# FRONT_PL_v1.net
KiCad netlist of a schematic drawn in Altium Designer
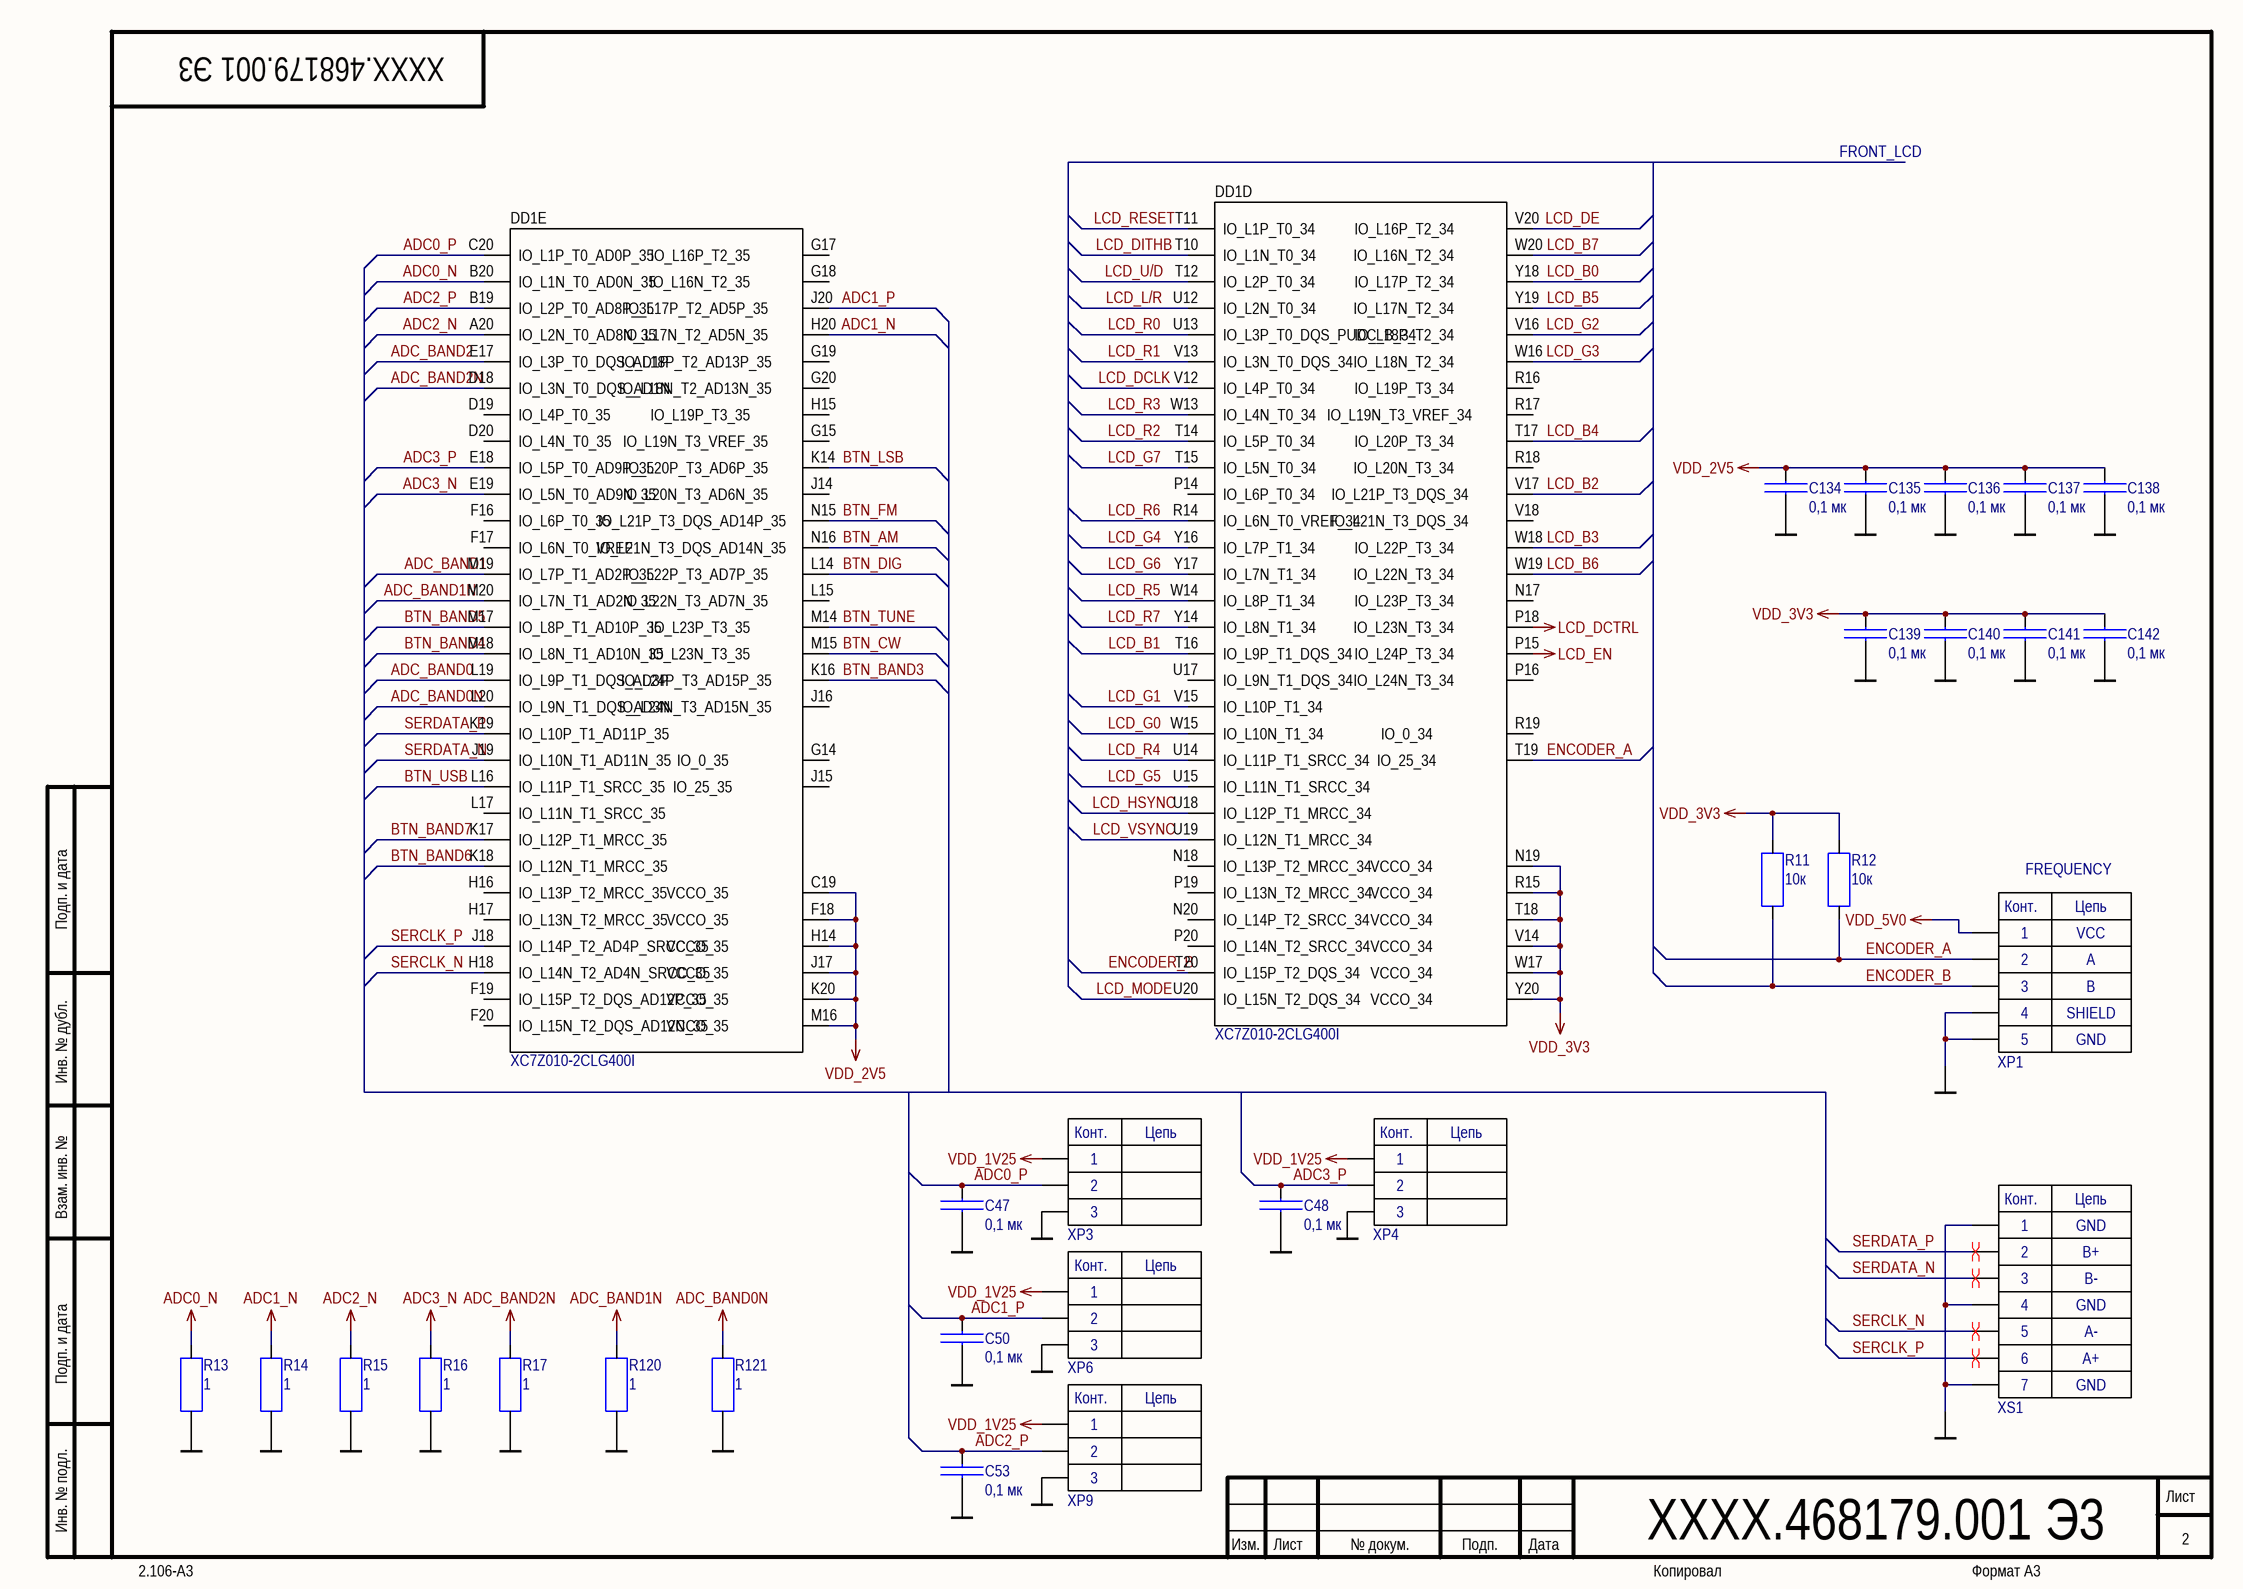
[diagram p0: FRONT_PL_v1.SchDoc]

(export (version "E")
  (design (tool "Eeschema 10.0.6"))
  (components
    (comp (ref "C47")
      (value "CC0402KRX5R6BB104")
      (footprint "CAPC1005X05L")
      (description "ЧИП конденсатор")
      (fields
        (field (name "NOMINAL") "0,1 мк")
        (field (name "MANUFACTURER") "Yageo")
        (field (name "TOLERANCE") "10%")
      )
      (libsource (lib "Database_Gost") (part "Capacitor const"))
    )
    (comp (ref "C48")
      (value "CC0402KRX5R6BB104")
      (footprint "CAPC1005X05L")
      (description "ЧИП конденсатор")
      (fields
        (field (name "NOMINAL") "0,1 мк")
        (field (name "MANUFACTURER") "Yageo")
        (field (name "TOLERANCE") "10%")
      )
      (libsource (lib "Database_Gost") (part "Capacitor const"))
    )
    (comp (ref "C50")
      (value "CC0402KRX5R6BB104")
      (footprint "CAPC1005X05L")
      (description "ЧИП конденсатор")
      (fields
        (field (name "NOMINAL") "0,1 мк")
        (field (name "MANUFACTURER") "Yageo")
        (field (name "TOLERANCE") "10%")
      )
      (libsource (lib "Database_Gost") (part "Capacitor const"))
    )
    (comp (ref "C53")
      (value "CC0402KRX5R6BB104")
      (footprint "CAPC1005X05L")
      (description "ЧИП конденсатор")
      (fields
        (field (name "NOMINAL") "0,1 мк")
        (field (name "MANUFACTURER") "Yageo")
        (field (name "TOLERANCE") "10%")
      )
      (libsource (lib "Database_Gost") (part "Capacitor const"))
    )
    (comp (ref "C134")
      (value "CC0402KRX5R6BB104")
      (footprint "CAPC1005X05L")
      (description "ЧИП конденсатор")
      (fields
        (field (name "NOMINAL") "0,1 мк")
        (field (name "MANUFACTURER") "Yageo")
        (field (name "TOLERANCE") "10%")
      )
      (libsource (lib "Database_Gost") (part "Capacitor const"))
    )
    (comp (ref "C135")
      (value "CC0402KRX5R6BB104")
      (footprint "CAPC1005X05L")
      (description "ЧИП конденсатор")
      (fields
        (field (name "NOMINAL") "0,1 мк")
        (field (name "MANUFACTURER") "Yageo")
        (field (name "TOLERANCE") "10%")
      )
      (libsource (lib "Database_Gost") (part "Capacitor const"))
    )
    (comp (ref "C136")
      (value "CC0402KRX5R6BB104")
      (footprint "CAPC1005X05L")
      (description "ЧИП конденсатор")
      (fields
        (field (name "NOMINAL") "0,1 мк")
        (field (name "MANUFACTURER") "Yageo")
        (field (name "TOLERANCE") "10%")
      )
      (libsource (lib "Database_Gost") (part "Capacitor const"))
    )
    (comp (ref "C137")
      (value "CC0402KRX5R6BB104")
      (footprint "CAPC1005X05L")
      (description "ЧИП конденсатор")
      (fields
        (field (name "NOMINAL") "0,1 мк")
        (field (name "MANUFACTURER") "Yageo")
        (field (name "TOLERANCE") "10%")
      )
      (libsource (lib "Database_Gost") (part "Capacitor const"))
    )
    (comp (ref "C138")
      (value "CC0402KRX5R6BB104")
      (footprint "CAPC1005X05L")
      (description "ЧИП конденсатор")
      (fields
        (field (name "NOMINAL") "0,1 мк")
        (field (name "MANUFACTURER") "Yageo")
        (field (name "TOLERANCE") "10%")
      )
      (libsource (lib "Database_Gost") (part "Capacitor const"))
    )
    (comp (ref "C139")
      (value "CC0402KRX5R6BB104")
      (footprint "CAPC1005X05L")
      (description "ЧИП конденсатор")
      (fields
        (field (name "NOMINAL") "0,1 мк")
        (field (name "MANUFACTURER") "Yageo")
        (field (name "TOLERANCE") "10%")
      )
      (libsource (lib "Database_Gost") (part "Capacitor const"))
    )
    (comp (ref "C140")
      (value "CC0402KRX5R6BB104")
      (footprint "CAPC1005X05L")
      (description "ЧИП конденсатор")
      (fields
        (field (name "NOMINAL") "0,1 мк")
        (field (name "MANUFACTURER") "Yageo")
        (field (name "TOLERANCE") "10%")
      )
      (libsource (lib "Database_Gost") (part "Capacitor const"))
    )
    (comp (ref "C141")
      (value "CC0402KRX5R6BB104")
      (footprint "CAPC1005X05L")
      (description "ЧИП конденсатор")
      (fields
        (field (name "NOMINAL") "0,1 мк")
        (field (name "MANUFACTURER") "Yageo")
        (field (name "TOLERANCE") "10%")
      )
      (libsource (lib "Database_Gost") (part "Capacitor const"))
    )
    (comp (ref "C142")
      (value "CC0402KRX5R6BB104")
      (footprint "CAPC1005X05L")
      (description "ЧИП конденсатор")
      (fields
        (field (name "NOMINAL") "0,1 мк")
        (field (name "MANUFACTURER") "Yageo")
        (field (name "TOLERANCE") "10%")
      )
      (libsource (lib "Database_Gost") (part "Capacitor const"))
    )
    (comp (ref "DD1")
      (value "XC7Z010-2CLG400I")
      (footprint "BGA400C80P20X20_1700X1700X147")
      (description "Zynq®-7000 SoC Family")
      (fields (field (name "MANUFACTURER") "Xilinx"))
      (libsource (lib "Chips_single") (part "XC7Z010-2CLG400I"))
    )
    (comp (ref "R11")
      (value "RC0402JR-0710KL")
      (footprint "RESC1005X04L")
      (description "ЧИП резистор")
      (fields
        (field (name "NOMINAL") "10к")
        (field (name "MANUFACTURER") "Yageo")
        (field (name "TOLERANCE") "5%")
      )
      (libsource (lib "Database_Gost") (part "Resistor const"))
    )
    (comp (ref "R12")
      (value "RC0402JR-0710KL")
      (footprint "RESC1005X04L")
      (description "ЧИП резистор")
      (fields
        (field (name "NOMINAL") "10к")
        (field (name "MANUFACTURER") "Yageo")
        (field (name "TOLERANCE") "5%")
      )
      (libsource (lib "Database_Gost") (part "Resistor const"))
    )
    (comp (ref "R13")
      (value "RC0402JR-071RL")
      (footprint "RESC1005X04L")
      (description "ЧИП резистор")
      (fields
        (field (name "NOMINAL") "1")
        (field (name "MANUFACTURER") "Yageo")
        (field (name "TOLERANCE") "5%")
      )
      (libsource (lib "Database_Gost") (part "Resistor const"))
    )
    (comp (ref "R14")
      (value "RC0402JR-071RL")
      (footprint "RESC1005X04L")
      (description "ЧИП резистор")
      (fields
        (field (name "NOMINAL") "1")
        (field (name "MANUFACTURER") "Yageo")
        (field (name "TOLERANCE") "5%")
      )
      (libsource (lib "Database_Gost") (part "Resistor const"))
    )
    (comp (ref "R15")
      (value "RC0402JR-071RL")
      (footprint "RESC1005X04L")
      (description "ЧИП резистор")
      (fields
        (field (name "NOMINAL") "1")
        (field (name "MANUFACTURER") "Yageo")
        (field (name "TOLERANCE") "5%")
      )
      (libsource (lib "Database_Gost") (part "Resistor const"))
    )
    (comp (ref "R16")
      (value "RC0402JR-071RL")
      (footprint "RESC1005X04L")
      (description "ЧИП резистор")
      (fields
        (field (name "NOMINAL") "1")
        (field (name "MANUFACTURER") "Yageo")
        (field (name "TOLERANCE") "5%")
      )
      (libsource (lib "Database_Gost") (part "Resistor const"))
    )
    (comp (ref "R17")
      (value "RC0402JR-071RL")
      (footprint "RESC1005X04L")
      (description "ЧИП резистор")
      (fields
        (field (name "NOMINAL") "1")
        (field (name "MANUFACTURER") "Yageo")
        (field (name "TOLERANCE") "5%")
      )
      (libsource (lib "Database_Gost") (part "Resistor const"))
    )
    (comp (ref "R120")
      (value "RC0402JR-071RL")
      (footprint "RESC1005X04L")
      (description "ЧИП резистор")
      (fields
        (field (name "NOMINAL") "1")
        (field (name "MANUFACTURER") "Yageo")
        (field (name "TOLERANCE") "5%")
      )
      (libsource (lib "Database_Gost") (part "Resistor const"))
    )
    (comp (ref "R121")
      (value "RC0402JR-071RL")
      (footprint "RESC1005X04L")
      (description "ЧИП резистор")
      (fields
        (field (name "NOMINAL") "1")
        (field (name "MANUFACTURER") "Yageo")
        (field (name "TOLERANCE") "5%")
      )
      (libsource (lib "Database_Gost") (part "Resistor const"))
    )
    (comp (ref "XP1")
      (value "WB-05")
      (footprint "WB-05 (MW-5M) pitch 2.00mm")
      (description "WB-05 (MW-5M) pitch 2.00mm\r\nDS1066-05M")
      (libsource (lib "Connectors") (part "WB-05"))
    )
    (comp (ref "XP3")
      (value "WB-03")
      (footprint "WB-03 (MW-3M) PITCH 2.00MM")
      (description "WB-03(MW-3M) pitch 2.00mm\r\nDS1066-03M")
      (libsource (lib "Connectors") (part "WB-03"))
    )
    (comp (ref "XP4")
      (value "WB-03")
      (footprint "WB-03 (MW-3M) PITCH 2.00MM")
      (description "WB-03(MW-3M) pitch 2.00mm\r\nDS1066-03M")
      (libsource (lib "Connectors") (part "WB-03"))
    )
    (comp (ref "XP6")
      (value "WB-03")
      (footprint "WB-03 (MW-3M) PITCH 2.00MM")
      (description "WB-03(MW-3M) pitch 2.00mm\r\nDS1066-03M")
      (libsource (lib "Connectors") (part "WB-03"))
    )
    (comp (ref "XP9")
      (value "WB-03")
      (footprint "WB-03 (MW-3M) PITCH 2.00MM")
      (description "WB-03(MW-3M) pitch 2.00mm\r\nDS1066-03M")
      (libsource (lib "Connectors") (part "WB-03"))
    )
    (comp (ref "XS1")
      (value "KLS1-SATA001")
      (footprint "KLS1-SATA001")
      (description "SATA Type A 7P Male Connector,SMD")
      (libsource (lib "Connectors") (part "SATA KLS1-SATA001"))
    )
  )
  (nets
    (net (code "1") (name "/ADC0_P") (class "Default")
      (node (ref "C47") (pin "2") (pinfunction "2_2") (pintype "passive"))
      (node (ref "DD1") (pin "C20") (pinfunction "IO_L1P_T0_AD0P_35_C20") (pintype "passive"))
      (node (ref "XP3") (pin "2") (pinfunction "2_2") (pintype "passive"))
    )
    (net (code "2") (name "/ADC1_P") (class "Default")
      (node (ref "C50") (pin "2") (pinfunction "2_2") (pintype "passive"))
      (node (ref "DD1") (pin "J20") (pinfunction "IO_L17P_T2_AD5P_35_J20") (pintype "passive"))
      (node (ref "XP6") (pin "2") (pinfunction "2_2") (pintype "passive"))
    )
    (net (code "3") (name "/ADC2_P") (class "Default")
      (node (ref "C53") (pin "2") (pinfunction "2_2") (pintype "passive"))
      (node (ref "DD1") (pin "B19") (pinfunction "IO_L2P_T0_AD8P_35_B19") (pintype "passive"))
      (node (ref "XP9") (pin "2") (pinfunction "2_2") (pintype "passive"))
    )
    (net (code "4") (name "/ADC3_P") (class "Default")
      (node (ref "C48") (pin "2") (pinfunction "2_2") (pintype "passive"))
      (node (ref "DD1") (pin "E18") (pinfunction "IO_L5P_T0_AD9P_35_E18") (pintype "passive"))
      (node (ref "XP4") (pin "2") (pinfunction "2_2") (pintype "passive"))
    )
    (net (code "5") (name "/ADC_BAND0") (class "Default")
      (node (ref "DD1") (pin "L19") (pinfunction "IO_L9P_T1_DQS_AD3P_L19") (pintype "passive"))
    )
    (net (code "6") (name "/ADC_BAND1") (class "Default")
      (node (ref "DD1") (pin "M19") (pinfunction "IO_L7P_T1_AD2P_35_M19") (pintype "passive"))
    )
    (net (code "7") (name "/ADC_BAND2") (class "Default")
      (node (ref "DD1") (pin "E17") (pinfunction "IO_L3P_T0_DQS_AD1P_E17") (pintype "passive"))
    )
    (net (code "8") (name "/BTN_AM") (class "Default")
      (node (ref "DD1") (pin "N16") (pinfunction "IO_L21N_T3_DQS_AD14N_35_N16") (pintype "passive"))
    )
    (net (code "9") (name "/BTN_BAND3") (class "Default")
      (node (ref "DD1") (pin "K16") (pinfunction "IO_L24P_T3_AD15P_35_K16") (pintype "passive"))
    )
    (net (code "10") (name "/BTN_BAND4") (class "Default")
      (node (ref "DD1") (pin "M18") (pinfunction "IO_L8N_T1_AD10N_35_M18") (pintype "passive"))
    )
    (net (code "11") (name "/BTN_BAND5") (class "Default")
      (node (ref "DD1") (pin "M17") (pinfunction "IO_L8P_T1_AD10P_35_M17") (pintype "passive"))
    )
    (net (code "12") (name "/BTN_BAND6") (class "Default")
      (node (ref "DD1") (pin "K18") (pinfunction "IO_L12N_T1_MRCC_35_K18") (pintype "passive"))
    )
    (net (code "13") (name "/BTN_BAND7") (class "Default")
      (node (ref "DD1") (pin "K17") (pinfunction "IO_L12P_T1_MRCC_35_K17") (pintype "passive"))
    )
    (net (code "14") (name "/BTN_CW") (class "Default")
      (node (ref "DD1") (pin "M15") (pinfunction "IO_L23N_T3_35_M15") (pintype "passive"))
    )
    (net (code "15") (name "/BTN_DIG") (class "Default")
      (node (ref "DD1") (pin "L14") (pinfunction "IO_L22P_T3_AD7P_35_L14") (pintype "passive"))
    )
    (net (code "16") (name "/BTN_FM") (class "Default")
      (node (ref "DD1") (pin "N15") (pinfunction "IO_L21P_T3_DQS_AD14P_35_N15") (pintype "passive"))
    )
    (net (code "17") (name "/BTN_LSB") (class "Default")
      (node (ref "DD1") (pin "K14") (pinfunction "IO_L20P_T3_AD6P_35_K14") (pintype "passive"))
    )
    (net (code "18") (name "/BTN_TUNE") (class "Default")
      (node (ref "DD1") (pin "M14") (pinfunction "IO_L23P_T3_35_M14") (pintype "passive"))
    )
    (net (code "19") (name "/BTN_USB") (class "Default")
      (node (ref "DD1") (pin "L16") (pinfunction "IO_L11P_T1_SRCC_35_L16") (pintype "passive"))
    )
    (net (code "20") (name "/ENCODER_A") (class "Default")
      (node (ref "DD1") (pin "T19") (pinfunction "IO_25_34_T19") (pintype "open_collector"))
      (node (ref "R12") (pin "2") (pinfunction "2_2") (pintype "passive"))
      (node (ref "XP1") (pin "2") (pinfunction "2_2") (pintype "passive"))
    )
    (net (code "21") (name "/ENCODER_B") (class "Default")
      (node (ref "DD1") (pin "T20") (pinfunction "IO_L15P_T2_DQS_34_T20") (pintype "open_collector"))
      (node (ref "R11") (pin "2") (pinfunction "2_2") (pintype "passive"))
      (node (ref "XP1") (pin "3") (pinfunction "3_3") (pintype "passive"))
    )
    (net (code "22") (name "/LCD_B0") (class "Default")
      (node (ref "DD1") (pin "Y18") (pinfunction "IO_L17P_T2_34_Y18") (pintype "open_collector"))
    )
    (net (code "23") (name "/LCD_B1") (class "Default")
      (node (ref "DD1") (pin "T16") (pinfunction "IO_L9P_T1_DQS_34_T16") (pintype "open_collector"))
    )
    (net (code "24") (name "/LCD_B2") (class "Default")
      (node (ref "DD1") (pin "V17") (pinfunction "IO_L21P_T3_DQS_34_V17") (pintype "open_collector"))
    )
    (net (code "25") (name "/LCD_B3") (class "Default")
      (node (ref "DD1") (pin "W18") (pinfunction "IO_L22P_T3_34_W18") (pintype "open_collector"))
    )
    (net (code "26") (name "/LCD_B4") (class "Default")
      (node (ref "DD1") (pin "T17") (pinfunction "IO_L20P_T3_34_T17") (pintype "open_collector"))
    )
    (net (code "27") (name "/LCD_B5") (class "Default")
      (node (ref "DD1") (pin "Y19") (pinfunction "IO_L17N_T2_34_Y19") (pintype "open_collector"))
    )
    (net (code "28") (name "/LCD_B6") (class "Default")
      (node (ref "DD1") (pin "W19") (pinfunction "IO_L22N_T3_34_W19") (pintype "open_collector"))
    )
    (net (code "29") (name "/LCD_B7") (class "Default")
      (node (ref "DD1") (pin "W20") (pinfunction "IO_L16N_T2_34_W20") (pintype "open_collector"))
    )
    (net (code "30") (name "/LCD_DCLK") (class "Default")
      (node (ref "DD1") (pin "V12") (pinfunction "IO_L4P_T0_34_V12") (pintype "open_collector"))
    )
    (net (code "31") (name "/LCD_DE") (class "Default")
      (node (ref "DD1") (pin "V20") (pinfunction "IO_L16P_T2_34_V20") (pintype "open_collector"))
    )
    (net (code "32") (name "/LCD_DITHB") (class "Default")
      (node (ref "DD1") (pin "T10") (pinfunction "IO_L1N_T0_34_T10") (pintype "open_collector"))
    )
    (net (code "33") (name "/LCD_G0") (class "Default")
      (node (ref "DD1") (pin "W15") (pinfunction "IO_L10N_T1_34_W15") (pintype "open_collector"))
    )
    (net (code "34") (name "/LCD_G1") (class "Default")
      (node (ref "DD1") (pin "V15") (pinfunction "IO_L10P_T1_34_V15") (pintype "open_collector"))
    )
    (net (code "35") (name "/LCD_G2") (class "Default")
      (node (ref "DD1") (pin "V16") (pinfunction "IO_L18P_T2_34_V16") (pintype "open_collector"))
    )
    (net (code "36") (name "/LCD_G3") (class "Default")
      (node (ref "DD1") (pin "W16") (pinfunction "IO_L18N_T2_34_W16") (pintype "open_collector"))
    )
    (net (code "37") (name "/LCD_G4") (class "Default")
      (node (ref "DD1") (pin "Y16") (pinfunction "IO_L7P_T1_34_Y16") (pintype "open_collector"))
    )
    (net (code "38") (name "/LCD_G5") (class "Default")
      (node (ref "DD1") (pin "U15") (pinfunction "IO_L11N_T1_SRCC_34_U15") (pintype "open_collector"))
    )
    (net (code "39") (name "/LCD_G6") (class "Default")
      (node (ref "DD1") (pin "Y17") (pinfunction "IO_L7N_T1_34_Y17") (pintype "open_collector"))
    )
    (net (code "40") (name "/LCD_G7") (class "Default")
      (node (ref "DD1") (pin "T15") (pinfunction "IO_L5N_T0_34_T15") (pintype "open_collector"))
    )
    (net (code "41") (name "/LCD_HSYNC") (class "Default")
      (node (ref "DD1") (pin "U18") (pinfunction "IO_L12P_T1_MRCC_34_U18") (pintype "open_collector"))
    )
    (net (code "42") (name "/LCD_L{slash}R") (class "Default")
      (node (ref "DD1") (pin "U12") (pinfunction "IO_L2N_T0_34_U12") (pintype "open_collector"))
    )
    (net (code "43") (name "/LCD_MODE") (class "Default")
      (node (ref "DD1") (pin "U20") (pinfunction "IO_L15N_T2_DQS_34_U20") (pintype "open_collector"))
    )
    (net (code "44") (name "/LCD_R0") (class "Default")
      (node (ref "DD1") (pin "U13") (pinfunction "IO_L3P_T0_DQS_PUDC_B_34_U13") (pintype "open_collector"))
    )
    (net (code "45") (name "/LCD_R1") (class "Default")
      (node (ref "DD1") (pin "V13") (pinfunction "IO_L3N_T0_DQS_34_V13") (pintype "open_collector"))
    )
    (net (code "46") (name "/LCD_R2") (class "Default")
      (node (ref "DD1") (pin "T14") (pinfunction "IO_L5P_T0_34_T14") (pintype "open_collector"))
    )
    (net (code "47") (name "/LCD_R3") (class "Default")
      (node (ref "DD1") (pin "W13") (pinfunction "IO_L4N_T0_34_W13") (pintype "open_collector"))
    )
    (net (code "48") (name "/LCD_R4") (class "Default")
      (node (ref "DD1") (pin "U14") (pinfunction "IO_L11P_T1_SRCC_34_U14") (pintype "open_collector"))
    )
    (net (code "49") (name "/LCD_R5") (class "Default")
      (node (ref "DD1") (pin "W14") (pinfunction "IO_L8P_T1_34_W14") (pintype "open_collector"))
    )
    (net (code "50") (name "/LCD_R6") (class "Default")
      (node (ref "DD1") (pin "R14") (pinfunction "IO_L6N_T0_VREF_34_R14") (pintype "open_collector"))
    )
    (net (code "51") (name "/LCD_R7") (class "Default")
      (node (ref "DD1") (pin "Y14") (pinfunction "IO_L8N_T1_34_Y14") (pintype "open_collector"))
    )
    (net (code "52") (name "/LCD_RESET") (class "Default")
      (node (ref "DD1") (pin "T11") (pinfunction "IO_L1P_T0_34_T11") (pintype "open_collector"))
    )
    (net (code "53") (name "/LCD_U{slash}D") (class "Default")
      (node (ref "DD1") (pin "T12") (pinfunction "IO_L2P_T0_34_T12") (pintype "open_collector"))
    )
    (net (code "54") (name "/LCD_VSYNC") (class "Default")
      (node (ref "DD1") (pin "U19") (pinfunction "IO_L12N_T1_MRCC_34_U19") (pintype "open_collector"))
    )
    (net (code "55") (name "/SERCLK_N") (class "Default")
      (node (ref "DD1") (pin "H18") (pinfunction "IO_L14N_T2_AD4N_SRCC_35_H18") (pintype "passive"))
      (node (ref "XS1") (pin "5") (pinfunction "5_5") (pintype "passive"))
    )
    (net (code "56") (name "/SERCLK_P") (class "Default")
      (node (ref "DD1") (pin "J18") (pinfunction "IO_L14P_T2_AD4P_SRCC_35_J18") (pintype "passive"))
      (node (ref "XS1") (pin "6") (pinfunction "6_6") (pintype "passive"))
    )
    (net (code "57") (name "/SERDATA_N") (class "Default")
      (node (ref "DD1") (pin "J19") (pinfunction "IO_L10N_T1_AD11N_35_J19") (pintype "passive"))
      (node (ref "XS1") (pin "3") (pinfunction "3_3") (pintype "passive"))
    )
    (net (code "58") (name "/SERDATA_P") (class "Default")
      (node (ref "DD1") (pin "K19") (pinfunction "IO_L10P_T1_AD11P_35_K19") (pintype "passive"))
      (node (ref "XS1") (pin "2") (pinfunction "2_2") (pintype "passive"))
    )
    (net (code "59") (name "ADC0_N") (class "Default")
      (node (ref "DD1") (pin "B20") (pinfunction "IO_L1N_T0_AD0N_35_B20") (pintype "passive"))
      (node (ref "R13") (pin "2") (pinfunction "2_2") (pintype "passive"))
    )
    (net (code "60") (name "ADC1_N") (class "Default")
      (node (ref "DD1") (pin "H20") (pinfunction "IO_L17N_T2_AD5N_35_H20") (pintype "passive"))
      (node (ref "R14") (pin "2") (pinfunction "2_2") (pintype "passive"))
    )
    (net (code "61") (name "ADC2_N") (class "Default")
      (node (ref "DD1") (pin "A20") (pinfunction "IO_L2N_T0_AD8N_35_A20") (pintype "passive"))
      (node (ref "R15") (pin "2") (pinfunction "2_2") (pintype "passive"))
    )
    (net (code "62") (name "ADC3_N") (class "Default")
      (node (ref "DD1") (pin "E19") (pinfunction "IO_L5N_T0_AD9N_35_E19") (pintype "passive"))
      (node (ref "R16") (pin "2") (pinfunction "2_2") (pintype "passive"))
    )
    (net (code "63") (name "ADC_BAND0N") (class "Default")
      (node (ref "DD1") (pin "L20") (pinfunction "IO_L9N_T1_DQS_AD3N_L20") (pintype "passive"))
      (node (ref "R121") (pin "2") (pinfunction "2_2") (pintype "passive"))
    )
    (net (code "64") (name "ADC_BAND1N") (class "Default")
      (node (ref "DD1") (pin "M20") (pinfunction "IO_L7N_T1_AD2N_35_M20") (pintype "passive"))
      (node (ref "R120") (pin "2") (pinfunction "2_2") (pintype "passive"))
    )
    (net (code "65") (name "ADC_BAND2N") (class "Default")
      (node (ref "DD1") (pin "D18") (pinfunction "IO_L3N_T0_DQS_AD1N_D18") (pintype "passive"))
      (node (ref "R17") (pin "2") (pinfunction "2_2") (pintype "passive"))
    )
    (net (code "66") (name "GND") (class "Default")
      (node (ref "C134") (pin "1") (pinfunction "1_1") (pintype "passive"))
      (node (ref "C135") (pin "1") (pinfunction "1_1") (pintype "passive"))
      (node (ref "C136") (pin "1") (pinfunction "1_1") (pintype "passive"))
      (node (ref "C137") (pin "1") (pinfunction "1_1") (pintype "passive"))
      (node (ref "C138") (pin "1") (pinfunction "1_1") (pintype "passive"))
      (node (ref "C139") (pin "1") (pinfunction "1_1") (pintype "passive"))
      (node (ref "C140") (pin "1") (pinfunction "1_1") (pintype "passive"))
      (node (ref "C141") (pin "1") (pinfunction "1_1") (pintype "passive"))
      (node (ref "C142") (pin "1") (pinfunction "1_1") (pintype "passive"))
      (node (ref "C47") (pin "1") (pinfunction "1_1") (pintype "passive"))
      (node (ref "C48") (pin "1") (pinfunction "1_1") (pintype "passive"))
      (node (ref "C50") (pin "1") (pinfunction "1_1") (pintype "passive"))
      (node (ref "C53") (pin "1") (pinfunction "1_1") (pintype "passive"))
      (node (ref "R120") (pin "1") (pinfunction "1_1") (pintype "passive"))
      (node (ref "R121") (pin "1") (pinfunction "1_1") (pintype "passive"))
      (node (ref "R13") (pin "1") (pinfunction "1_1") (pintype "passive"))
      (node (ref "R14") (pin "1") (pinfunction "1_1") (pintype "passive"))
      (node (ref "R15") (pin "1") (pinfunction "1_1") (pintype "passive"))
      (node (ref "R16") (pin "1") (pinfunction "1_1") (pintype "passive"))
      (node (ref "R17") (pin "1") (pinfunction "1_1") (pintype "passive"))
      (node (ref "XP1") (pin "4") (pinfunction "4_4") (pintype "passive"))
      (node (ref "XP1") (pin "5") (pinfunction "5_5") (pintype "passive"))
      (node (ref "XP3") (pin "3") (pinfunction "3_3") (pintype "passive"))
      (node (ref "XP4") (pin "3") (pinfunction "3_3") (pintype "passive"))
      (node (ref "XP6") (pin "3") (pinfunction "3_3") (pintype "passive"))
      (node (ref "XP9") (pin "3") (pinfunction "3_3") (pintype "passive"))
      (node (ref "XS1") (pin "1") (pinfunction "1_1") (pintype "passive"))
      (node (ref "XS1") (pin "4") (pinfunction "4_4") (pintype "passive"))
      (node (ref "XS1") (pin "7") (pinfunction "7_7") (pintype "passive"))
    )
    (net (code "67") (name "LCD_DCTRL") (class "Default")
      (node (ref "DD1") (pin "P18") (pinfunction "IO_L23N_T3_34_P18") (pintype "open_collector"))
    )
    (net (code "68") (name "LCD_EN") (class "Default")
      (node (ref "DD1") (pin "P15") (pinfunction "IO_L24P_T3_34_P15") (pintype "open_collector"))
    )
    (net (code "69") (name "VDD_1V25") (class "Default")
      (node (ref "XP3") (pin "1") (pinfunction "1_1") (pintype "passive"))
      (node (ref "XP4") (pin "1") (pinfunction "1_1") (pintype "passive"))
      (node (ref "XP6") (pin "1") (pinfunction "1_1") (pintype "passive"))
      (node (ref "XP9") (pin "1") (pinfunction "1_1") (pintype "passive"))
    )
    (net (code "70") (name "VDD_2V5") (class "Default")
      (node (ref "C134") (pin "2") (pinfunction "2_2") (pintype "passive"))
      (node (ref "C135") (pin "2") (pinfunction "2_2") (pintype "passive"))
      (node (ref "C136") (pin "2") (pinfunction "2_2") (pintype "passive"))
      (node (ref "C137") (pin "2") (pinfunction "2_2") (pintype "passive"))
      (node (ref "C138") (pin "2") (pinfunction "2_2") (pintype "passive"))
      (node (ref "DD1") (pin "C19") (pinfunction "VCCO_35_C19") (pintype "passive"))
      (node (ref "DD1") (pin "F18") (pinfunction "VCCO_35_F18") (pintype "passive"))
      (node (ref "DD1") (pin "H14") (pinfunction "VCCO_35_H14") (pintype "passive"))
      (node (ref "DD1") (pin "J17") (pinfunction "VCCO_35_J17") (pintype "passive"))
      (node (ref "DD1") (pin "K20") (pinfunction "VCCO_35_K20") (pintype "passive"))
      (node (ref "DD1") (pin "M16") (pinfunction "VCCO_35_M16") (pintype "passive"))
    )
    (net (code "71") (name "VDD_3V3") (class "Default")
      (node (ref "C139") (pin "2") (pinfunction "2_2") (pintype "passive"))
      (node (ref "C140") (pin "2") (pinfunction "2_2") (pintype "passive"))
      (node (ref "C141") (pin "2") (pinfunction "2_2") (pintype "passive"))
      (node (ref "C142") (pin "2") (pinfunction "2_2") (pintype "passive"))
      (node (ref "DD1") (pin "N19") (pinfunction "VCCO_34_N19") (pintype "open_collector"))
      (node (ref "DD1") (pin "R15") (pinfunction "VCCO_34_R15") (pintype "open_collector"))
      (node (ref "DD1") (pin "T18") (pinfunction "VCCO_34_T18") (pintype "open_collector"))
      (node (ref "DD1") (pin "V14") (pinfunction "VCCO_34_V14") (pintype "open_collector"))
      (node (ref "DD1") (pin "W17") (pinfunction "VCCO_34_W17") (pintype "open_collector"))
      (node (ref "DD1") (pin "Y20") (pinfunction "VCCO_34_Y20") (pintype "open_collector"))
      (node (ref "R11") (pin "1") (pinfunction "1_1") (pintype "passive"))
      (node (ref "R12") (pin "1") (pinfunction "1_1") (pintype "passive"))
    )
    (net (code "72") (name "VDD_5V0") (class "Default")
      (node (ref "XP1") (pin "1") (pinfunction "1_1") (pintype "passive"))
    )
    (net (code "73") (name "unconnected-(DD1D-IO_0_34-PadR19)") (class "Default")
      (node (ref "DD1") (pin "R19") (pinfunction "IO_0_34_R19") (pintype "open_collector"))
    )
    (net (code "74") (name "unconnected-(DD1D-IO_L6P_T0_34-PadP14)") (class "Default")
      (node (ref "DD1") (pin "P14") (pinfunction "IO_L6P_T0_34_P14") (pintype "open_collector"))
    )
    (net (code "75") (name "unconnected-(DD1D-IO_L9N_T1_DQS_34-PadU17)") (class "Default")
      (node (ref "DD1") (pin "U17") (pinfunction "IO_L9N_T1_DQS_34_U17") (pintype "open_collector"))
    )
    (net (code "76") (name "unconnected-(DD1D-IO_L13N_T2_MRCC_34-PadP19)") (class "Default")
      (node (ref "DD1") (pin "P19") (pinfunction "IO_L13N_T2_MRCC_34_P19") (pintype "open_collector"))
    )
    (net (code "77") (name "unconnected-(DD1D-IO_L13P_T2_MRCC_34-PadN18)") (class "Default")
      (node (ref "DD1") (pin "N18") (pinfunction "IO_L13P_T2_MRCC_34_N18") (pintype "open_collector"))
    )
    (net (code "78") (name "unconnected-(DD1D-IO_L14N_T2_SRCC_34-PadP20)") (class "Default")
      (node (ref "DD1") (pin "P20") (pinfunction "IO_L14N_T2_SRCC_34_P20") (pintype "open_collector"))
    )
    (net (code "79") (name "unconnected-(DD1D-IO_L14P_T2_SRCC_34-PadN20)") (class "Default")
      (node (ref "DD1") (pin "N20") (pinfunction "IO_L14P_T2_SRCC_34_N20") (pintype "open_collector"))
    )
    (net (code "80") (name "unconnected-(DD1D-IO_L19N_T3_VREF_34-PadR17)") (class "Default")
      (node (ref "DD1") (pin "R17") (pinfunction "IO_L19N_T3_VREF_34_R17") (pintype "open_collector"))
    )
    (net (code "81") (name "unconnected-(DD1D-IO_L19P_T3_34-PadR16)") (class "Default")
      (node (ref "DD1") (pin "R16") (pinfunction "IO_L19P_T3_34_R16") (pintype "open_collector"))
    )
    (net (code "82") (name "unconnected-(DD1D-IO_L20N_T3_34-PadR18)") (class "Default")
      (node (ref "DD1") (pin "R18") (pinfunction "IO_L20N_T3_34_R18") (pintype "open_collector"))
    )
    (net (code "83") (name "unconnected-(DD1D-IO_L21N_T3_DQS_34-PadV18)") (class "Default")
      (node (ref "DD1") (pin "V18") (pinfunction "IO_L21N_T3_DQS_34_V18") (pintype "open_collector"))
    )
    (net (code "84") (name "unconnected-(DD1D-IO_L23P_T3_34-PadN17)") (class "Default")
      (node (ref "DD1") (pin "N17") (pinfunction "IO_L23P_T3_34_N17") (pintype "open_collector"))
    )
    (net (code "85") (name "unconnected-(DD1D-IO_L24N_T3_34-PadP16)") (class "Default")
      (node (ref "DD1") (pin "P16") (pinfunction "IO_L24N_T3_34_P16") (pintype "open_collector"))
    )
    (net (code "86") (name "unconnected-(DD1E-IO_0_35-PadG14)") (class "Default")
      (node (ref "DD1") (pin "G14") (pinfunction "IO_0_35_G14") (pintype "passive"))
    )
    (net (code "87") (name "unconnected-(DD1E-IO_25_35-PadJ15)") (class "Default")
      (node (ref "DD1") (pin "J15") (pinfunction "IO_25_35_J15") (pintype "passive"))
    )
    (net (code "88") (name "unconnected-(DD1E-IO_L4N_T0_35-PadD20)") (class "Default")
      (node (ref "DD1") (pin "D20") (pinfunction "IO_L4N_T0_35_D20") (pintype "passive"))
    )
    (net (code "89") (name "unconnected-(DD1E-IO_L4P_T0_35-PadD19)") (class "Default")
      (node (ref "DD1") (pin "D19") (pinfunction "IO_L4P_T0_35_D19") (pintype "passive"))
    )
    (net (code "90") (name "unconnected-(DD1E-IO_L6N_T0_VREF-PadF17)") (class "Default")
      (node (ref "DD1") (pin "F17") (pinfunction "IO_L6N_T0_VREF_F17") (pintype "passive"))
    )
    (net (code "91") (name "unconnected-(DD1E-IO_L6P_T0_35-PadF16)") (class "Default")
      (node (ref "DD1") (pin "F16") (pinfunction "IO_L6P_T0_35_F16") (pintype "passive"))
    )
    (net (code "92") (name "unconnected-(DD1E-IO_L11N_T1_SRCC_35-PadL17)") (class "Default")
      (node (ref "DD1") (pin "L17") (pinfunction "IO_L11N_T1_SRCC_35_L17") (pintype "passive"))
    )
    (net (code "93") (name "unconnected-(DD1E-IO_L13N_T2_MRCC_35-PadH17)") (class "Default")
      (node (ref "DD1") (pin "H17") (pinfunction "IO_L13N_T2_MRCC_35_H17") (pintype "passive"))
    )
    (net (code "94") (name "unconnected-(DD1E-IO_L13P_T2_MRCC_35-PadH16)") (class "Default")
      (node (ref "DD1") (pin "H16") (pinfunction "IO_L13P_T2_MRCC_35_H16") (pintype "passive"))
    )
    (net (code "95") (name "unconnected-(DD1E-IO_L15N_T2_DQS_AD12N_35-PadF20)") (class "Default")
      (node (ref "DD1") (pin "F20") (pinfunction "IO_L15N_T2_DQS_AD12N_35_F20") (pintype "passive"))
    )
    (net (code "96") (name "unconnected-(DD1E-IO_L15P_T2_DQS_AD12P_35-PadF19)") (class "Default")
      (node (ref "DD1") (pin "F19") (pinfunction "IO_L15P_T2_DQS_AD12P_35_F19") (pintype "passive"))
    )
    (net (code "97") (name "unconnected-(DD1E-IO_L16N_T2_35-PadG18)") (class "Default")
      (node (ref "DD1") (pin "G18") (pinfunction "IO_L16N_T2_35_G18") (pintype "passive"))
    )
    (net (code "98") (name "unconnected-(DD1E-IO_L16P_T2_35-PadG17)") (class "Default")
      (node (ref "DD1") (pin "G17") (pinfunction "IO_L16P_T2_35_G17") (pintype "passive"))
    )
    (net (code "99") (name "unconnected-(DD1E-IO_L18N_T2_AD13N_35-PadG20)") (class "Default")
      (node (ref "DD1") (pin "G20") (pinfunction "IO_L18N_T2_AD13N_35_G20") (pintype "passive"))
    )
    (net (code "100") (name "unconnected-(DD1E-IO_L18P_T2_AD13P_35-PadG19)") (class "Default")
      (node (ref "DD1") (pin "G19") (pinfunction "IO_L18P_T2_AD13P_35_G19") (pintype "passive"))
    )
    (net (code "101") (name "unconnected-(DD1E-IO_L19N_T3_VREF_35-PadG15)") (class "Default")
      (node (ref "DD1") (pin "G15") (pinfunction "IO_L19N_T3_VREF_35_G15") (pintype "passive"))
    )
    (net (code "102") (name "unconnected-(DD1E-IO_L19P_T3_35-PadH15)") (class "Default")
      (node (ref "DD1") (pin "H15") (pinfunction "IO_L19P_T3_35_H15") (pintype "passive"))
    )
    (net (code "103") (name "unconnected-(DD1E-IO_L20N_T3_AD6N_35-PadJ14)") (class "Default")
      (node (ref "DD1") (pin "J14") (pinfunction "IO_L20N_T3_AD6N_35_J14") (pintype "passive"))
    )
    (net (code "104") (name "unconnected-(DD1E-IO_L22N_T3_AD7N_35-PadL15)") (class "Default")
      (node (ref "DD1") (pin "L15") (pinfunction "IO_L22N_T3_AD7N_35_L15") (pintype "passive"))
    )
    (net (code "105") (name "unconnected-(DD1E-IO_L24N_T3_AD15N_35-PadJ16)") (class "Default")
      (node (ref "DD1") (pin "J16") (pinfunction "IO_L24N_T3_AD15N_35_J16") (pintype "passive"))
    )
  )
)
